# 10_EEPROM.net
KiCad netlist of a schematic drawn in Altium Designer
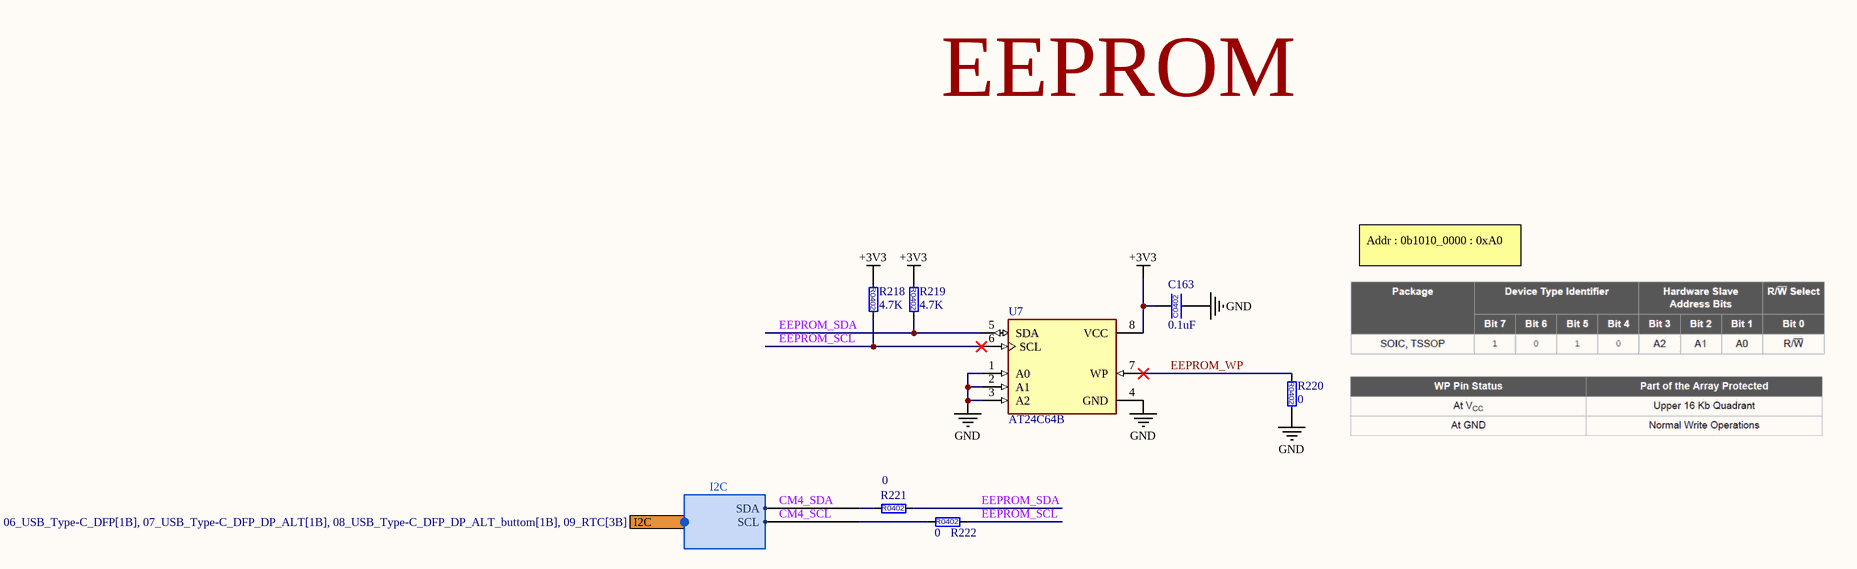
[diagram p0: 10_EEPROM.SchDoc]

(export (version "E")
  (design (tool "Eeschema 10.0.6"))
  (components
    (comp (ref "C163")
      (value "0.1uF")
      (footprint "C0402")
      (description "CAP CER  0.1uF 10% 25V X5R 0402")
      (fields
        (field (name "MANUFACTURER") "AVX Corporation")
        (field (name "MANUFACTURER PART NUMBER") "04023D104KAT2A")
      )
      (libsource (lib "Capacitor") (part "04023D104KAT2A"))
    )
    (comp (ref "R218")
      (value "4.7K")
      (footprint "R0402")
      (description "RES SMD 4.7K ohm 1% 1/16W R0402")
      (fields
        (field (name "MANUFACTURER") "Vishay Dale")
        (field (name "MANUFACTURER PART NUMBER") "CRCW04024K7FK")
      )
      (libsource (lib "Resistor") (part "CRCW04024K7FK"))
    )
    (comp (ref "R219")
      (value "4.7K")
      (footprint "R0402")
      (description "RES SMD 4.7K ohm 1% 1/16W R0402")
      (fields
        (field (name "MANUFACTURER") "Vishay Dale")
        (field (name "MANUFACTURER PART NUMBER") "CRCW04024K7FK")
      )
      (libsource (lib "Resistor") (part "CRCW04024K7FK"))
    )
    (comp (ref "R220")
      (value "0")
      (footprint "R0402")
      (description "RES SMD 0 ohm 1/16W R0402")
      (fields
        (field (name "MANUFACTURER") "Vishay Dale")
        (field (name "MANUFACTURER PART NUMBER") "CRCW04020000Z0")
      )
      (libsource (lib "Resistor") (part "CRCW04020000Z0"))
    )
    (comp (ref "R221")
      (value "0")
      (footprint "R0402")
      (description "RES SMD 0 ohm 1/16W R0402")
      (fields
        (field (name "MANUFACTURER") "Vishay Dale")
        (field (name "MANUFACTURER PART NUMBER") "CRCW04020000Z0")
      )
      (libsource (lib "Resistor") (part "CRCW04020000Z0"))
    )
    (comp (ref "R222")
      (value "0")
      (footprint "R0402")
      (description "RES SMD 0 ohm 1/16W R0402")
      (fields
        (field (name "MANUFACTURER") "Vishay Dale")
        (field (name "MANUFACTURER PART NUMBER") "CRCW04020000Z0")
      )
      (libsource (lib "Resistor") (part "CRCW04020000Z0"))
    )
    (comp (ref "U7")
      (value "AT24C64B")
      (footprint "AT24C64B_SOIC_8")
      (description "IC EEPROM 64K I2C 400KHZ 8SOIC")
      (fields
        (field (name "MANUFACTURER") "Microchip")
        (field (name "MANUFACTURER PART NUMBER") "AT24C64BN-10SU-2.7")
      )
      (libsource (lib "ic") (part "AT24C64B"))
    )
  )
  (nets
    (net (code "2") (name "+3V3") (class "Default")
      (node (ref "C163") (pin "1") (pinfunction "1_1") (pintype "passive"))
      (node (ref "R218") (pin "1") (pinfunction "1_1") (pintype "passive"))
      (node (ref "R219") (pin "1") (pinfunction "1_1") (pintype "passive"))
      (node (ref "U7") (pin "8") (pinfunction "VCC_8") (pintype "power_in"))
    )
    (net (code "3") (name "/CM4_SCL") (class "Default")
      (node (ref "R222") (pin "1") (pinfunction "1_1") (pintype "passive"))
    )
    (net (code "4") (name "/CM4_SDA") (class "Default")
      (node (ref "R221") (pin "1") (pinfunction "1_1") (pintype "passive"))
    )
    (net (code "5") (name "/EEPROM_SCL") (class "Default")
      (node (ref "R218") (pin "2") (pinfunction "2_2") (pintype "passive"))
      (node (ref "R222") (pin "2") (pinfunction "2_2") (pintype "passive"))
      (node (ref "U7") (pin "6") (pinfunction "SCL_6") (pintype "input"))
    )
    (net (code "6") (name "/EEPROM_SDA") (class "Default")
      (node (ref "R219") (pin "2") (pinfunction "2_2") (pintype "passive"))
      (node (ref "R221") (pin "2") (pinfunction "2_2") (pintype "passive"))
      (node (ref "U7") (pin "5") (pinfunction "SDA_5") (pintype "bidirectional"))
    )
    (net (code "7") (name "/EEPROM_WP") (class "Default")
      (node (ref "R220") (pin "1") (pinfunction "1_1") (pintype "passive"))
      (node (ref "U7") (pin "7") (pinfunction "WP_7") (pintype "input"))
    )
    (net (code "9") (name "GND") (class "Default")
      (node (ref "C163") (pin "2") (pinfunction "2_2") (pintype "passive"))
      (node (ref "R220") (pin "2") (pinfunction "2_2") (pintype "passive"))
      (node (ref "U7") (pin "1") (pinfunction "A0_1") (pintype "input"))
      (node (ref "U7") (pin "2") (pinfunction "A1_2") (pintype "input"))
      (node (ref "U7") (pin "3") (pinfunction "A2_3") (pintype "input"))
      (node (ref "U7") (pin "4") (pinfunction "GND_4") (pintype "power_in"))
    )
  )
)
